# soundthings.net
KiCad netlist of a schematic drawn in EAGLE
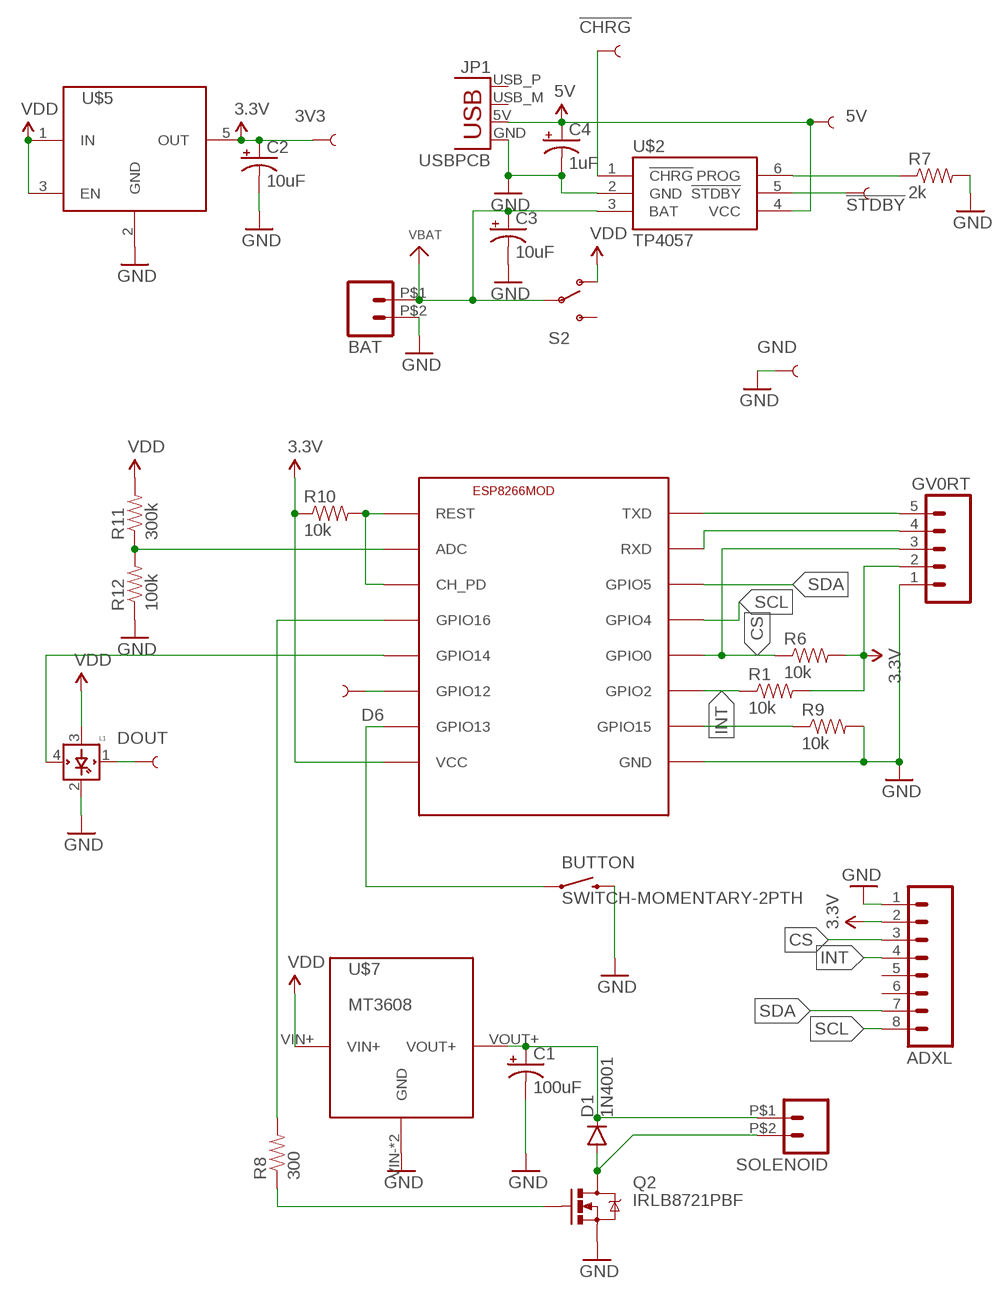
[diagram p0: schematic, sheet 1]

(export (version "E")
  (design (tool "Eeschema 10.0.6"))
  (components
    (comp (ref "!CHRG")
      (value "TEST-POINTTP_15TH_THRU")
      (footprint "eagle-import:TP_15TH")
      (libsource (lib "eagle-import") (part "TEST-POINTTP_15TH_THRU"))
    )
    (comp (ref "!STDBY")
      (value "TEST-POINTTP_15TH_THRU")
      (footprint "eagle-import:TP_15TH")
      (libsource (lib "eagle-import") (part "TEST-POINTTP_15TH_THRU"))
    )
    (comp (ref "3V3")
      (value "TEST-POINTTP_15TH_THRU")
      (footprint "eagle-import:TP_15TH")
      (libsource (lib "eagle-import") (part "TEST-POINTTP_15TH_THRU"))
    )
    (comp (ref "5V")
      (value "TEST-POINTTP_15TH_THRU")
      (footprint "eagle-import:TP_15TH")
      (libsource (lib "eagle-import") (part "TEST-POINTTP_15TH_THRU"))
    )
    (comp (ref "ADXL")
      (value "M08LOCK")
      (footprint "eagle-import:1X08_LOCK")
      (libsource (lib "eagle-import") (part "M08LOCK"))
    )
    (comp (ref "BAT")
      (value "M02PTH2")
      (footprint "eagle-import:1X02_BIG")
      (libsource (lib "eagle-import") (part "M02PTH2"))
    )
    (comp (ref "BUTTON")
      (value "SWITCH-MOMENTARY-2PTH")
      (footprint "eagle-import:TACTILE-PTH")
      (libsource (lib "eagle-import") (part "SWITCH-MOMENTARY-2PTH"))
    )
    (comp (ref "C1")
      (value "100uF")
      (footprint "eagle-import:CPOL-RADIAL-100UF-25V")
      (libsource (lib "eagle-import") (part "100UF-25V-20%(PTH)"))
    )
    (comp (ref "C2")
      (value "10uF")
      (footprint "eagle-import:CPOL-RADIAL-100UF-25V")
      (libsource (lib "eagle-import") (part "100UF-25V-20%(PTH)"))
    )
    (comp (ref "C3")
      (value "10uF")
      (footprint "eagle-import:CPOL-RADIAL-100UF-25V")
      (libsource (lib "eagle-import") (part "100UF-25V-20%(PTH)"))
    )
    (comp (ref "C4")
      (value "1uF")
      (footprint "eagle-import:CPOL-RADIAL-100UF-25V")
      (libsource (lib "eagle-import") (part "100UF-25V-20%(PTH)"))
    )
    (comp (ref "D1")
      (value "1N4001")
      (footprint "eagle-import:DIODE-1N4148")
      (libsource (lib "eagle-import") (part "DIODE1N4148"))
    )
    (comp (ref "D6")
      (value "TEST-POINTTP_15TH_THRU")
      (footprint "eagle-import:TP_15TH")
      (libsource (lib "eagle-import") (part "TEST-POINTTP_15TH_THRU"))
    )
    (comp (ref "DOUT")
      (value "TEST-POINTTP_15TH_THRU")
      (footprint "eagle-import:TP_15TH")
      (libsource (lib "eagle-import") (part "TEST-POINTTP_15TH_THRU"))
    )
    (comp (ref "ESP8266MOD")
      (value "ESP8266-07")
      (footprint "eagle-import:ESP-07")
      (libsource (lib "eagle-import") (part "ESP8266-07"))
    )
    (comp (ref "GND")
      (value "TEST-POINTTP_15TH_THRU")
      (footprint "eagle-import:TP_15TH")
      (libsource (lib "eagle-import") (part "TEST-POINTTP_15TH_THRU"))
    )
    (comp (ref "GV0RT")
      (value "M05LOCK")
      (footprint "eagle-import:1X05_LOCK")
      (libsource (lib "eagle-import") (part "M05LOCK"))
    )
    (comp (ref "JP1")
      (value "USBPCB")
      (footprint "eagle-import:USB-A-PCB")
      (libsource (lib "eagle-import") (part "USBPCB"))
    )
    (comp (ref "L1")
      (value "WS2812BTH")
      (footprint "eagle-import:WS2812F5")
      (libsource (lib "eagle-import") (part "WS2812BTH"))
    )
    (comp (ref "Q2")
      (value "IRLB8721PBF")
      (footprint "eagle-import:TO220V")
      (libsource (lib "eagle-import") (part "MOSFET-NCHANNELFQP30N06L"))
    )
    (comp (ref "R1")
      (value "10k")
      (footprint "eagle-import:AXIAL-0.3")
      (libsource (lib "eagle-import") (part "RESISTORAXIAL-0.3"))
    )
    (comp (ref "R6")
      (value "10k")
      (footprint "eagle-import:AXIAL-0.3")
      (libsource (lib "eagle-import") (part "RESISTORAXIAL-0.3"))
    )
    (comp (ref "R7")
      (value "2k")
      (footprint "eagle-import:AXIAL-0.3")
      (libsource (lib "eagle-import") (part "RESISTORAXIAL-0.3"))
    )
    (comp (ref "R8")
      (value "300")
      (footprint "eagle-import:AXIAL-0.3")
      (libsource (lib "eagle-import") (part "RESISTORAXIAL-0.3"))
    )
    (comp (ref "R9")
      (value "10k")
      (footprint "eagle-import:AXIAL-0.3")
      (libsource (lib "eagle-import") (part "RESISTORAXIAL-0.3"))
    )
    (comp (ref "R10")
      (value "10k")
      (footprint "eagle-import:AXIAL-0.3")
      (libsource (lib "eagle-import") (part "RESISTORAXIAL-0.3"))
    )
    (comp (ref "R11")
      (value "300k")
      (footprint "eagle-import:AXIAL-0.3")
      (libsource (lib "eagle-import") (part "RESISTORAXIAL-0.3"))
    )
    (comp (ref "R12")
      (value "100k")
      (footprint "eagle-import:AXIAL-0.3")
      (libsource (lib "eagle-import") (part "RESISTORAXIAL-0.3"))
    )
    (comp (ref "S2")
      (value "SWITCH-SPDT-1")
      (footprint "eagle-import:MHS122-1")
      (libsource (lib "eagle-import") (part "SWITCH-SPDT-1"))
    )
    (comp (ref "SOLENOID")
      (value "M02PTH2")
      (footprint "eagle-import:1X02_BIG")
      (libsource (lib "eagle-import") (part "M02PTH2"))
    )
    (comp (ref "U$2")
      (value "TP4057")
      (footprint "eagle-import:SOT23-6")
      (libsource (lib "eagle-import") (part "TP4057SOT-26-R"))
    )
    (comp (ref "U$5")
      (value "TLV70233")
      (footprint "eagle-import:SOT23-5")
      (libsource (lib "eagle-import") (part "TLV70233"))
    )
    (comp (ref "U$7")
      (value "MT3608")
      (footprint "eagle-import:MT3608")
      (libsource (lib "eagle-import") (part "MT3608"))
    )
  )
  (nets
    (net (code "1") (name "3.3V") (class "Default")
      (node (ref "3V3") (pin "P$1") (pinfunction "1_P$1") (pintype "bidirectional"))
      (node (ref "ADXL") (pin "2") (pinfunction "2_2") (pintype "passive"))
      (node (ref "C2") (pin "1") (pinfunction "+_1") (pintype "passive"))
      (node (ref "ESP8266MOD") (pin "VCC") (pinfunction "VCC_VCC") (pintype "power_in"))
      (node (ref "GV0RT") (pin "2") (pinfunction "2_2") (pintype "passive"))
      (node (ref "R1") (pin "P$2") (pinfunction "2_P$2") (pintype "passive"))
      (node (ref "R10") (pin "P$1") (pinfunction "1_P$1") (pintype "passive"))
      (node (ref "R6") (pin "P$2") (pinfunction "2_P$2") (pintype "passive"))
      (node (ref "U$5") (pin "5") (pinfunction "OUT_5") (pintype "power_in"))
    )
    (net (code "2") (name "5V") (class "Default")
      (node (ref "5V") (pin "P$1") (pinfunction "1_P$1") (pintype "bidirectional"))
      (node (ref "C4") (pin "1") (pinfunction "+_1") (pintype "passive"))
      (node (ref "JP1") (pin "5V") (pinfunction "VBUS_5V") (pintype "bidirectional"))
      (node (ref "U$2") (pin "4") (pinfunction "VCC_4") (pintype "power_in"))
    )
    (net (code "3") (name "CS") (class "Default")
      (node (ref "ADXL") (pin "3") (pinfunction "3_3") (pintype "passive"))
      (node (ref "ESP8266MOD") (pin "GPIO0") (pinfunction "GPIO0_GPIO0") (pintype "bidirectional"))
      (node (ref "GV0RT") (pin "3") (pinfunction "3_3") (pintype "passive"))
      (node (ref "R6") (pin "P$1") (pinfunction "1_P$1") (pintype "passive"))
    )
    (net (code "4") (name "GND") (class "Default")
      (node (ref "ADXL") (pin "1") (pinfunction "1_1") (pintype "passive"))
      (node (ref "BAT") (pin "P$2") (pinfunction "2_P$2") (pintype "passive"))
      (node (ref "BUTTON") (pin "3") (pinfunction "2_3") (pintype "passive"))
      (node (ref "C1") (pin "2") (pinfunction "-_2") (pintype "passive"))
      (node (ref "C2") (pin "2") (pinfunction "-_2") (pintype "passive"))
      (node (ref "C3") (pin "2") (pinfunction "-_2") (pintype "passive"))
      (node (ref "C4") (pin "2") (pinfunction "-_2") (pintype "passive"))
      (node (ref "ESP8266MOD") (pin "GND") (pinfunction "GND_GND") (pintype "power_in"))
      (node (ref "GND") (pin "P$1") (pinfunction "1_P$1") (pintype "bidirectional"))
      (node (ref "GV0RT") (pin "1") (pinfunction "1_1") (pintype "passive"))
      (node (ref "JP1") (pin "GND") (pinfunction "GND_GND") (pintype "bidirectional"))
      (node (ref "L1") (pin "2") (pinfunction "GND_2") (pintype "bidirectional"))
      (node (ref "Q2") (pin "3") (pinfunction "S_3") (pintype "passive"))
      (node (ref "R12") (pin "P$1") (pinfunction "1_P$1") (pintype "passive"))
      (node (ref "R7") (pin "P$2") (pinfunction "2_P$2") (pintype "passive"))
      (node (ref "R9") (pin "P$2") (pinfunction "2_P$2") (pintype "passive"))
      (node (ref "U$2") (pin "2") (pinfunction "GND_2") (pintype "power_in"))
      (node (ref "U$5") (pin "2") (pinfunction "GND_2") (pintype "power_in"))
      (node (ref "U$7") (pin "VIN-") (pinfunction "GND_VIN-") (pintype "power_in"))
      (node (ref "U$7") (pin "VOUT-") (pinfunction "GND_VOUT-") (pintype "power_in"))
    )
    (net (code "5") (name "INT") (class "Default")
      (node (ref "ADXL") (pin "4") (pinfunction "4_4") (pintype "passive"))
      (node (ref "ESP8266MOD") (pin "GPIO2") (pinfunction "GPIO2_GPIO2") (pintype "bidirectional"))
      (node (ref "R1") (pin "P$1") (pinfunction "1_P$1") (pintype "passive"))
    )
    (net (code "6") (name "Net-(!CHRG-1)") (class "Default")
      (node (ref "!CHRG") (pin "P$1") (pinfunction "1_P$1") (pintype "bidirectional"))
      (node (ref "U$2") (pin "1") (pinfunction "~{CHRG}_1") (pintype "open_collector"))
    )
    (net (code "7") (name "Net-(!STDBY-1)") (class "Default")
      (node (ref "!STDBY") (pin "P$1") (pinfunction "1_P$1") (pintype "bidirectional"))
      (node (ref "U$2") (pin "5") (pinfunction "~{STDBY}_5") (pintype "open_collector"))
    )
    (net (code "8") (name "Net-(BUTTON-Pad1)") (class "Default")
      (node (ref "BUTTON") (pin "1") (pinfunction "1_1") (pintype "passive"))
      (node (ref "ESP8266MOD") (pin "GPIO13") (pinfunction "GPIO13_GPIO13") (pintype "bidirectional"))
    )
    (net (code "9") (name "Net-(C1-+)") (class "Default")
      (node (ref "C1") (pin "1") (pinfunction "+_1") (pintype "passive"))
      (node (ref "D1") (pin "C") (pinfunction "C_C") (pintype "passive"))
      (node (ref "SOLENOID") (pin "P$1") (pinfunction "1_P$1") (pintype "passive"))
      (node (ref "U$7") (pin "VOUT+") (pinfunction "VOUT+_VOUT+") (pintype "power_in"))
    )
    (net (code "10") (name "Net-(D6-1)") (class "Default")
      (node (ref "D6") (pin "P$1") (pinfunction "1_P$1") (pintype "bidirectional"))
      (node (ref "ESP8266MOD") (pin "GPIO12") (pinfunction "GPIO12_GPIO12") (pintype "bidirectional"))
    )
    (net (code "11") (name "Net-(DOUT-1)") (class "Default")
      (node (ref "DOUT") (pin "P$1") (pinfunction "1_P$1") (pintype "bidirectional"))
      (node (ref "L1") (pin "1") (pinfunction "DOUT_1") (pintype "output"))
    )
    (net (code "12") (name "Net-(ESP8266MOD-PadRXD)") (class "Default")
      (node (ref "ESP8266MOD") (pin "RXD") (pinfunction "RXD_RXD") (pintype "input"))
      (node (ref "GV0RT") (pin "4") (pinfunction "4_4") (pintype "passive"))
    )
    (net (code "13") (name "Net-(ESP8266MOD-PadTXD)") (class "Default")
      (node (ref "ESP8266MOD") (pin "TXD") (pinfunction "TXD_TXD") (pintype "output"))
      (node (ref "GV0RT") (pin "5") (pinfunction "5_5") (pintype "passive"))
    )
    (net (code "14") (name "Net-(L1-DIN)") (class "Default")
      (node (ref "ESP8266MOD") (pin "GPIO14") (pinfunction "GPIO14_GPIO14") (pintype "bidirectional"))
      (node (ref "L1") (pin "4") (pinfunction "DIN_4") (pintype "input"))
    )
    (net (code "15") (name "Net-(Q2-D)") (class "Default")
      (node (ref "D1") (pin "A") (pinfunction "A_A") (pintype "passive"))
      (node (ref "Q2") (pin "2") (pinfunction "D_2") (pintype "passive"))
      (node (ref "SOLENOID") (pin "P$2") (pinfunction "2_P$2") (pintype "passive"))
    )
    (net (code "16") (name "Net-(Q2-G)") (class "Default")
      (node (ref "Q2") (pin "1") (pinfunction "G_1") (pintype "passive"))
      (node (ref "R8") (pin "P$1") (pinfunction "1_P$1") (pintype "passive"))
    )
    (net (code "17") (name "Net-(R7-1)") (class "Default")
      (node (ref "R7") (pin "P$1") (pinfunction "1_P$1") (pintype "passive"))
      (node (ref "U$2") (pin "6") (pinfunction "PROG_6") (pintype "input"))
    )
    (net (code "18") (name "Net-(R8-2)") (class "Default")
      (node (ref "ESP8266MOD") (pin "GPIO16") (pinfunction "GPIO16_GPIO16") (pintype "bidirectional"))
      (node (ref "R8") (pin "P$2") (pinfunction "2_P$2") (pintype "passive"))
    )
    (net (code "19") (name "Net-(R9-1)") (class "Default")
      (node (ref "ESP8266MOD") (pin "GPIO15") (pinfunction "GPIO15_GPIO15") (pintype "input"))
      (node (ref "R9") (pin "P$1") (pinfunction "1_P$1") (pintype "passive"))
    )
    (net (code "20") (name "Net-(R10-2)") (class "Default")
      (node (ref "ESP8266MOD") (pin "CH_PD") (pinfunction "CH_PD_CH_PD") (pintype "input"))
      (node (ref "ESP8266MOD") (pin "REST") (pinfunction "REST_REST") (pintype "bidirectional"))
      (node (ref "R10") (pin "P$2") (pinfunction "2_P$2") (pintype "passive"))
    )
    (net (code "21") (name "Net-(R11-1)") (class "Default")
      (node (ref "ESP8266MOD") (pin "ADC") (pinfunction "ADC_ADC") (pintype "bidirectional"))
      (node (ref "R11") (pin "P$1") (pinfunction "1_P$1") (pintype "passive"))
      (node (ref "R12") (pin "P$2") (pinfunction "2_P$2") (pintype "passive"))
    )
    (net (code "22") (name "SCL") (class "Default")
      (node (ref "ADXL") (pin "8") (pinfunction "8_8") (pintype "passive"))
      (node (ref "ESP8266MOD") (pin "GPIO5") (pinfunction "GPIO4_GPIO5") (pintype "bidirectional"))
    )
    (net (code "23") (name "SDA") (class "Default")
      (node (ref "ADXL") (pin "7") (pinfunction "7_7") (pintype "passive"))
      (node (ref "ESP8266MOD") (pin "GPIO4") (pinfunction "GPIO5_GPIO4") (pintype "bidirectional"))
    )
    (net (code "24") (name "VBAT") (class "Default")
      (node (ref "BAT") (pin "P$1") (pinfunction "1_P$1") (pintype "passive"))
      (node (ref "C3") (pin "1") (pinfunction "+_1") (pintype "passive"))
      (node (ref "S2") (pin "2") (pinfunction "P_2") (pintype "passive"))
      (node (ref "U$2") (pin "3") (pinfunction "BAT_3") (pintype "power_in"))
    )
    (net (code "25") (name "VDD") (class "Default")
      (node (ref "L1") (pin "3") (pinfunction "VDD_3") (pintype "bidirectional"))
      (node (ref "R11") (pin "P$2") (pinfunction "2_P$2") (pintype "passive"))
      (node (ref "S2") (pin "1") (pinfunction "O_1") (pintype "passive"))
      (node (ref "U$5") (pin "1") (pinfunction "IN_1") (pintype "power_in"))
      (node (ref "U$5") (pin "3") (pinfunction "EN_3") (pintype "input"))
      (node (ref "U$7") (pin "VIN+") (pinfunction "VIN+_VIN+") (pintype "power_in"))
    )
    (net (code "26") (name "unconnected-(ADXL-Pad5)") (class "Default")
      (node (ref "ADXL") (pin "5") (pinfunction "5_5") (pintype "passive"))
    )
    (net (code "27") (name "unconnected-(ADXL-Pad6)") (class "Default")
      (node (ref "ADXL") (pin "6") (pinfunction "6_6") (pintype "passive"))
    )
    (net (code "28") (name "unconnected-(JP1-D+-PadUSB_P)") (class "Default")
      (node (ref "JP1") (pin "USB_P") (pinfunction "D+_USB_P") (pintype "bidirectional"))
    )
    (net (code "29") (name "unconnected-(JP1-D--PadUSB_M)") (class "Default")
      (node (ref "JP1") (pin "USB_M") (pinfunction "D-_USB_M") (pintype "bidirectional"))
    )
    (net (code "30") (name "unconnected-(S2-S-Pad3)") (class "Default")
      (node (ref "S2") (pin "3") (pinfunction "S_3") (pintype "passive"))
    )
  )
)
